# Power.net
KiCad netlist of a schematic drawn in Altium Designer
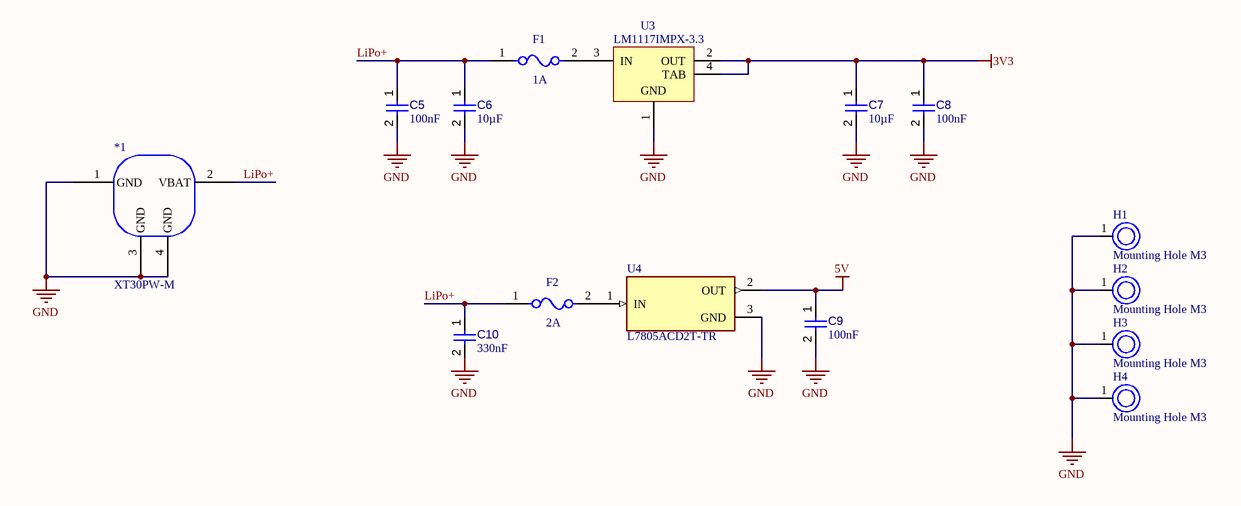
[diagram p0: Power.SchDoc]

(export (version "E")
  (design (tool "Eeschema 10.0.6"))
  (components
    (comp (ref "*1")
      (value "XT30PW-M")
      (footprint "XT30PW-M-Footprint-1")
      (description "XT30PW-M公头 Socket,DCsupply,XT30,male,PIN:2")
      (libsource (lib "PWr in Space team") (part "XT30PW-M-Symbol-1"))
    )
    (comp (ref "C5")
      (value "100nF")
      (footprint "CAPC2013X95X50NL10T25")
      (description "Chip Capacitor, 100 nF, +/- 10%, 50 V, 0805 (2012 Metric)")
      (fields (field (name "TOLERANCE") "10%") (field (name "Comment") "Capacitor 100 nF +/-10% 50 V 0805"))
      (libsource (lib "PWr in Space team") (part "CAP-NP-2"))
    )
    (comp (ref "C6")
      (value "10µF")
      (footprint "CAPC2013X135X45NL10T25")
      (description "Chip Capacitor, 10 uF, +/- 10%, 16 V, 0805 (2012 Metric)")
      (fields (field (name "TOLERANCE") "10%") (field (name "Comment") "Capacitor 10 uF +/- 10% 16 V 0805"))
      (libsource (lib "PWr in Space team") (part "CAP-NP-2"))
    )
    (comp (ref "C7")
      (value "10µF")
      (footprint "CAPC2013X135X45NL10T25")
      (description "Chip Capacitor, 10 uF, +/- 10%, 16 V, 0805 (2012 Metric)")
      (fields (field (name "TOLERANCE") "10%") (field (name "Comment") "Capacitor 10 uF +/- 10% 16 V 0805"))
      (libsource (lib "PWr in Space team") (part "CAP-NP-2"))
    )
    (comp (ref "C8")
      (value "100nF")
      (footprint "CAPC2013X95X50NL10T25")
      (description "Chip Capacitor, 100 nF, +/- 10%, 50 V, 0805 (2012 Metric)")
      (fields (field (name "TOLERANCE") "10%") (field (name "Comment") "Capacitor 100 nF +/-10% 50 V 0805"))
      (libsource (lib "PWr in Space team") (part "CAP-NP-2"))
    )
    (comp (ref "C9")
      (value "100nF")
      (footprint "CAPC2013X135X45NL10T25")
      (description "Chip Capacitor, 10 uF, +/- 10%, 16 V, 0805 (2012 Metric)")
      (fields (field (name "TOLERANCE") "10%") (field (name "Comment") "Capacitor 10 uF +/- 10% 16 V 0805"))
      (libsource (lib "PWr in Space team") (part "CAP-NP-2"))
    )
    (comp (ref "C10")
      (value "330nF")
      (footprint "CAPC2013X135X45NL10T25")
      (description "Chip Capacitor, 10 uF, +/- 10%, 16 V, 0805 (2012 Metric)")
      (fields (field (name "TOLERANCE") "10%") (field (name "Comment") "Capacitor 10 uF +/- 10% 16 V 0805"))
      (libsource (lib "PWr in Space team") (part "CAP-NP-2"))
    )
    (comp (ref "F1")
      (value "1A")
      (footprint "FP-0466-MFG")
      (description "FUSE BOARD MNT 1A 63VAC/VDC 1206")
      (fields
        (field (name "MANUFACTURER PART NUMBER") "0466001.NR")
        (field (name "MANUFACTURER") "Littelfuse Inc")
      )
      (libsource (lib "Altium Content Vault") (part "5bcf9b9f640e542cf0359d10258e979"))
    )
    (comp (ref "F2")
      (value "2A")
      (footprint "FP-0466-MFG")
      (description "FUSE BOARD MNT 1A 63VAC/VDC 1206")
      (fields
        (field (name "MANUFACTURER PART NUMBER") "0466001.NR")
        (field (name "MANUFACTURER") "Littelfuse Inc")
      )
      (libsource (lib "Altium Content Vault") (part "5bcf9b9f640e542cf0359d10258e979"))
    )
    (comp (ref "H1")
      (value "Mounting Hole M3")
      (footprint "Mounting_Hole_m3")
      (description "M3")
      (libsource (lib "PWr in Space team") (part "Mounting Hole M3"))
    )
    (comp (ref "H2")
      (value "Mounting Hole M3")
      (footprint "Mounting_Hole_m3")
      (description "M3")
      (libsource (lib "PWr in Space team") (part "Mounting Hole M3"))
    )
    (comp (ref "H3")
      (value "Mounting Hole M3")
      (footprint "Mounting_Hole_m3")
      (description "M3")
      (libsource (lib "PWr in Space team") (part "Mounting Hole M3"))
    )
    (comp (ref "H4")
      (value "Mounting Hole M3")
      (footprint "Mounting_Hole_m3")
      (description "M3")
      (libsource (lib "PWr in Space team") (part "Mounting Hole M3"))
    )
    (comp (ref "U3")
      (value "LM1117IMPX-3.3")
      (footprint "MP04A_M")
      (description "800mA Low-Dropout Linear Regulator, 4-pin SOT-223")
      (fields (field (name "MANUFACTURER") "National Semiconductor"))
      (libsource (lib "Altium Content Vault") (part "PM-REG-LM1086-SOT4"))
    )
    (comp (ref "U4")
      (value "L7805ACD2T-TR")
      (footprint "L7805ACD2T-TR:TO254P1515X470-3N")
      (description "Positive voltage regulator ICs")
      (fields (field (name "MF") "{'manufacturer': u'STMicroelectronics'}"))
      (libsource (lib "*") (part "L7805ACD2T-TR"))
    )
  )
  (nets
    (net (code "1") (name "/LiPo+") (class "Default")
      (node (ref "*1") (pin "2") (pinfunction "VBAT_2") (pintype "passive"))
      (node (ref "C10") (pin "1") (pinfunction "1_1") (pintype "passive"))
      (node (ref "C5") (pin "1") (pinfunction "1_1") (pintype "passive"))
      (node (ref "C6") (pin "1") (pinfunction "1_1") (pintype "passive"))
      (node (ref "F1") (pin "1") (pinfunction "1_1") (pintype "passive"))
      (node (ref "F2") (pin "1") (pinfunction "1_1") (pintype "passive"))
    )
    (net (code "2") (name "3V3") (class "Default")
      (node (ref "C7") (pin "1") (pinfunction "1_1") (pintype "passive"))
      (node (ref "C8") (pin "1") (pinfunction "1_1") (pintype "passive"))
      (node (ref "U3") (pin "2") (pinfunction "OUT_2") (pintype "power_in"))
      (node (ref "U3") (pin "4") (pinfunction "TAB_4") (pintype "power_in"))
    )
    (net (code "3") (name "5V") (class "Default")
      (node (ref "C9") (pin "1") (pinfunction "1_1") (pintype "passive"))
      (node (ref "U4") (pin "2") (pinfunction "OUT_2") (pintype "output"))
    )
    (net (code "4") (name "GND") (class "Default")
      (node (ref "*1") (pin "1") (pinfunction "GND_1") (pintype "passive"))
      (node (ref "*1") (pin "3") (pinfunction "GND_3") (pintype "passive"))
      (node (ref "*1") (pin "4") (pinfunction "GND_4") (pintype "passive"))
      (node (ref "C10") (pin "2") (pinfunction "2_2") (pintype "passive"))
      (node (ref "C5") (pin "2") (pinfunction "2_2") (pintype "passive"))
      (node (ref "C6") (pin "2") (pinfunction "2_2") (pintype "passive"))
      (node (ref "C7") (pin "2") (pinfunction "2_2") (pintype "passive"))
      (node (ref "C8") (pin "2") (pinfunction "2_2") (pintype "passive"))
      (node (ref "C9") (pin "2") (pinfunction "2_2") (pintype "passive"))
      (node (ref "H1") (pin "1") (pintype "passive"))
      (node (ref "H2") (pin "1") (pintype "passive"))
      (node (ref "H3") (pin "1") (pintype "passive"))
      (node (ref "H4") (pin "1") (pintype "passive"))
      (node (ref "U3") (pin "1") (pinfunction "GND_1") (pintype "power_in"))
      (node (ref "U4") (pin "3") (pinfunction "GND_3") (pintype "power_in"))
    )
    (net (code "5") (name "Net-(U3-IN)") (class "Default")
      (node (ref "F1") (pin "2") (pinfunction "2_2") (pintype "passive"))
      (node (ref "U3") (pin "3") (pinfunction "IN_3") (pintype "power_in"))
    )
    (net (code "6") (name "Net-(U4-IN)") (class "Default")
      (node (ref "F2") (pin "2") (pinfunction "2_2") (pintype "passive"))
      (node (ref "U4") (pin "1") (pinfunction "IN_1") (pintype "input"))
    )
  )
)
